# QCopterMV_POWER_Sch.net
KiCad netlist of a schematic drawn in Altium Designer
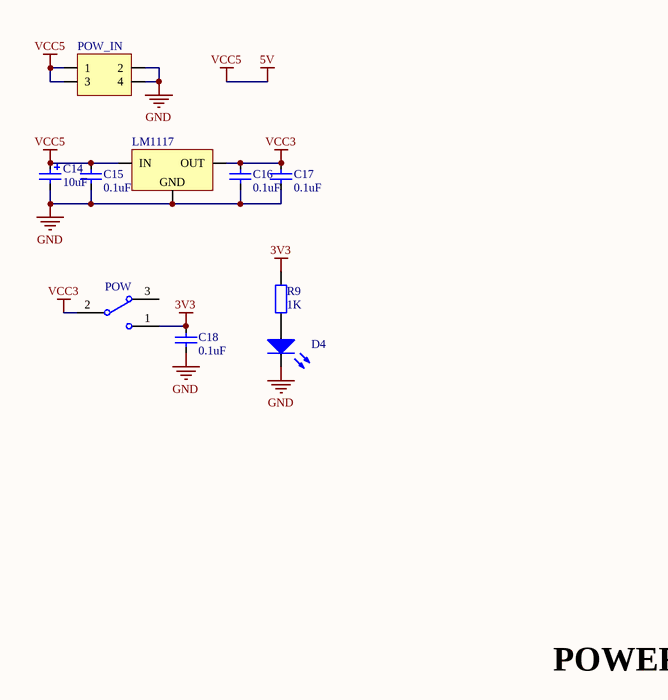
[diagram p0: QCopterMV_POWER_Sch.SchDoc]

(export (version "E")
  (design (tool "Eeschema 10.0.6"))
  (components
    (comp (ref "C14")
      (value "10uF")
      (footprint "PCB_Passive:CAP_TAN_B1210")
      (description "Capacitor")
      (fields (field (name "Comment") "Cap_Tan_1210"))
      (libsource (lib "SCH_Passive") (part "Cap_Tan_1210"))
    )
    (comp (ref "C15")
      (value "0.1uF")
      (footprint "PCB_Passive:CAP_0603")
      (description "Capacitor")
      (fields (field (name "Comment") "Cap_0603"))
      (libsource (lib "SCH_Passive") (part "Cap_0603"))
    )
    (comp (ref "C16")
      (value "0.1uF")
      (footprint "PCB_Passive:CAP_0603")
      (description "Capacitor")
      (fields (field (name "Comment") "Cap_0603"))
      (libsource (lib "SCH_Passive") (part "Cap_0603"))
    )
    (comp (ref "C17")
      (value "0.1uF")
      (footprint "PCB_Passive:CAP_0603")
      (description "Capacitor")
      (fields (field (name "Comment") "Cap_0603"))
      (libsource (lib "SCH_Passive") (part "Cap_0603"))
    )
    (comp (ref "C18")
      (value "0.1uF")
      (footprint "PCB_Passive:CAP_0603")
      (description "Capacitor")
      (fields (field (name "Comment") "Cap_0603"))
      (libsource (lib "SCH_Passive") (part "Cap_0603"))
    )
    (comp (ref "D4")
      (value "LED_0603_BLUE")
      (footprint "PCB_Active:LED_0603_BLUE")
      (description "LED")
      (libsource (lib "SCH_Active") (part "LED_0603_BLUE"))
    )
    (comp (ref "LM1")
      (value "LM1117")
      (footprint "PCB_IC:SOT223")
      (description "Power")
      (libsource (lib "SCH_IC") (part "LM1117"))
    )
    (comp (ref "POW")
      (value "SW-SPDT")
      (footprint "PCB_Switch:SW_T")
      (description "SPDT Subminiature Toggle Switch, Right Angle Mounting, Vertical Actuation")
      (fields (field (name "PUBLISHER") "Altium Limited"))
      (libsource (lib "SCH_Switch") (part "SW-SPDT_1"))
    )
    (comp (ref "POW_IN")
      (value "HDR2X2_90_2.54")
      (footprint "PCB_Connector:HDR2X2_90_2.54")
      (description "Header")
      (libsource (lib "SCH_Connector") (part "HDR2X2_90_2.54"))
    )
    (comp (ref "R9")
      (value "1K")
      (footprint "PCB_Passive:RES_0603")
      (description "Resistor")
      (fields (field (name "Comment") "Res_0603"))
      (libsource (lib "SCH_Passive") (part "Res_0603"))
    )
  )
  (nets
    (net (code "1") (name "3V3") (class "Default")
      (node (ref "C18") (pin "2") (pinfunction "2_2") (pintype "passive"))
      (node (ref "POW") (pin "1") (pinfunction "1_1") (pintype "passive"))
      (node (ref "R9") (pin "2") (pinfunction "2_2") (pintype "passive"))
    )
    (net (code "2") (name "5V") (class "Default")
      (node (ref "C14") (pin "1") (pinfunction "1_1") (pintype "passive"))
      (node (ref "C15") (pin "2") (pinfunction "2_2") (pintype "passive"))
      (node (ref "LM1") (pin "3") (pinfunction "IN_3") (pintype "power_in"))
      (node (ref "POW_IN") (pin "1") (pinfunction "1_1") (pintype "passive"))
      (node (ref "POW_IN") (pin "3") (pinfunction "3_3") (pintype "passive"))
    )
    (net (code "3") (name "GND") (class "Default")
      (node (ref "C14") (pin "2") (pinfunction "2_2") (pintype "passive"))
      (node (ref "C15") (pin "1") (pinfunction "1_1") (pintype "passive"))
      (node (ref "C16") (pin "1") (pinfunction "1_1") (pintype "passive"))
      (node (ref "C17") (pin "1") (pinfunction "1_1") (pintype "passive"))
      (node (ref "C18") (pin "1") (pinfunction "1_1") (pintype "passive"))
      (node (ref "D4") (pin "2") (pinfunction "K_2") (pintype "passive"))
      (node (ref "LM1") (pin "1") (pinfunction "GND_1") (pintype "power_in"))
      (node (ref "POW_IN") (pin "2") (pinfunction "2_2") (pintype "passive"))
      (node (ref "POW_IN") (pin "4") (pinfunction "4_4") (pintype "passive"))
    )
    (net (code "4") (name "Net-(D4-A)") (class "Default")
      (node (ref "D4") (pin "1") (pinfunction "A_1") (pintype "passive"))
      (node (ref "R9") (pin "1") (pinfunction "1_1") (pintype "passive"))
    )
    (net (code "5") (name "VCC3") (class "Default")
      (node (ref "C16") (pin "2") (pinfunction "2_2") (pintype "passive"))
      (node (ref "C17") (pin "2") (pinfunction "2_2") (pintype "passive"))
      (node (ref "LM1") (pin "2") (pinfunction "OUT_2") (pintype "power_in"))
      (node (ref "POW") (pin "2") (pinfunction "2_2") (pintype "passive"))
    )
    (net (code "6") (name "unconnected-(POW-Pad3)") (class "Default")
      (node (ref "POW") (pin "3") (pinfunction "3_3") (pintype "passive"))
    )
  )
)
